# LPC1769.net
KiCad netlist of a schematic drawn in Altium Designer
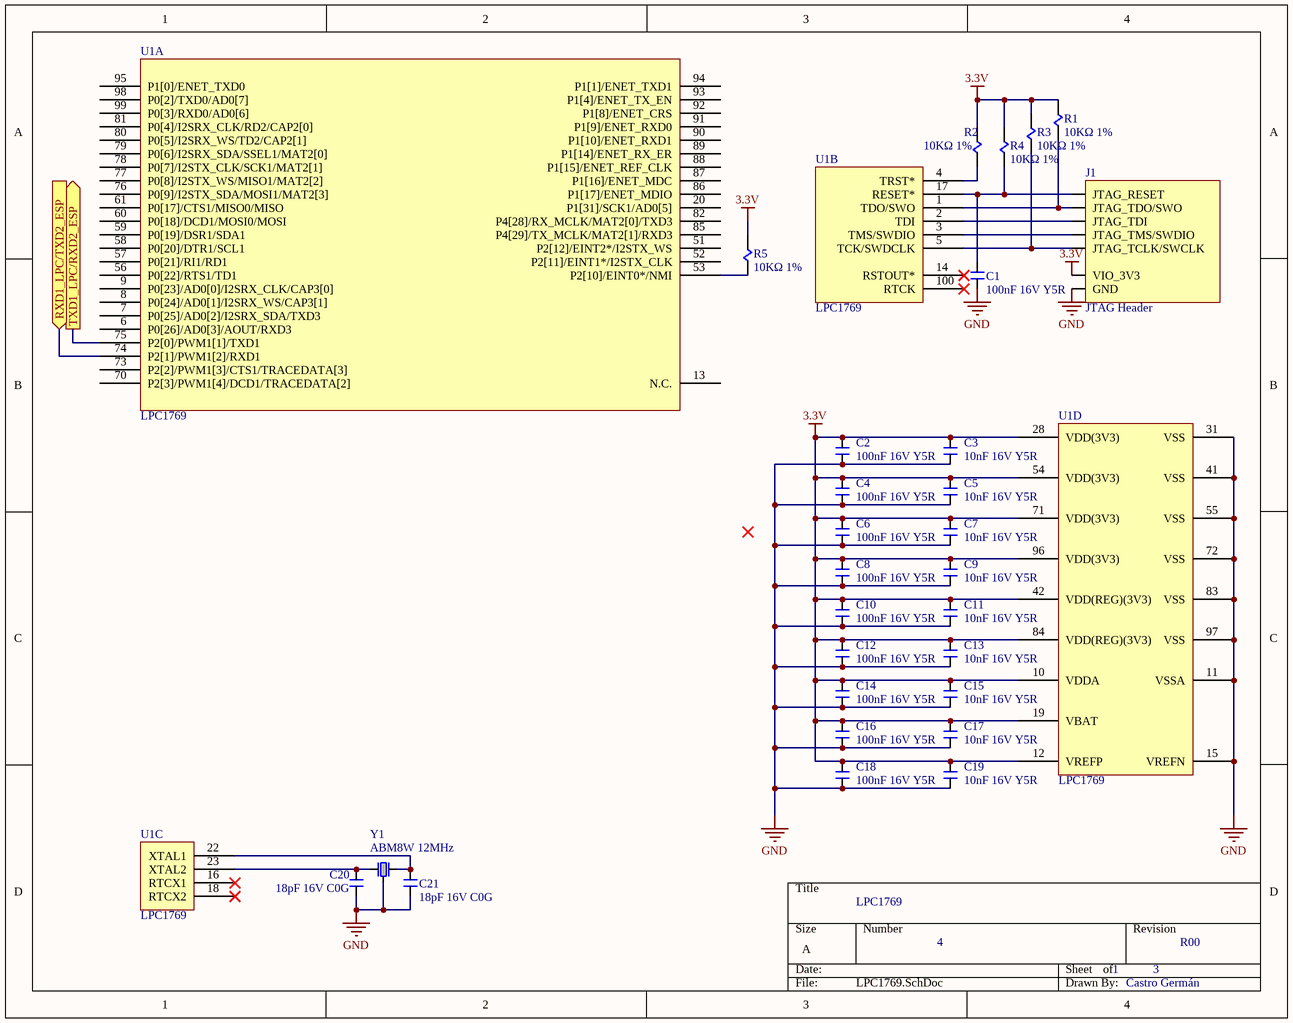
[diagram p0: LPC1769.SchDoc]

(export (version "E")
  (design (tool "Eeschema 10.0.6"))
  (components
    (comp (ref "C1")
      (value "100nF 16V Y5R")
      (footprint "C_0805")
      (description "Capacitor")
      (libsource (lib "MyPro") (part "Capacitor"))
    )
    (comp (ref "C2")
      (value "100nF 16V Y5R")
      (footprint "C_0805")
      (description "Capacitor")
      (libsource (lib "MyPro") (part "Capacitor"))
    )
    (comp (ref "C3")
      (value "10nF 16V Y5R")
      (footprint "C_0805")
      (description "Capacitor")
      (libsource (lib "MyPro") (part "Capacitor"))
    )
    (comp (ref "C4")
      (value "100nF 16V Y5R")
      (footprint "C_0805")
      (description "Capacitor")
      (libsource (lib "MyPro") (part "Capacitor"))
    )
    (comp (ref "C5")
      (value "10nF 16V Y5R")
      (footprint "C_0805")
      (description "Capacitor")
      (libsource (lib "MyPro") (part "Capacitor"))
    )
    (comp (ref "C6")
      (value "100nF 16V Y5R")
      (footprint "C_0805")
      (description "Capacitor")
      (libsource (lib "MyPro") (part "Capacitor"))
    )
    (comp (ref "C7")
      (value "10nF 16V Y5R")
      (footprint "C_0805")
      (description "Capacitor")
      (libsource (lib "MyPro") (part "Capacitor"))
    )
    (comp (ref "C8")
      (value "100nF 16V Y5R")
      (footprint "C_0805")
      (description "Capacitor")
      (libsource (lib "MyPro") (part "Capacitor"))
    )
    (comp (ref "C9")
      (value "10nF 16V Y5R")
      (footprint "C_0805")
      (description "Capacitor")
      (libsource (lib "MyPro") (part "Capacitor"))
    )
    (comp (ref "C10")
      (value "100nF 16V Y5R")
      (footprint "C_0805")
      (description "Capacitor")
      (libsource (lib "MyPro") (part "Capacitor"))
    )
    (comp (ref "C11")
      (value "10nF 16V Y5R")
      (footprint "C_0805")
      (description "Capacitor")
      (libsource (lib "MyPro") (part "Capacitor"))
    )
    (comp (ref "C12")
      (value "100nF 16V Y5R")
      (footprint "C_0805")
      (description "Capacitor")
      (libsource (lib "MyPro") (part "Capacitor"))
    )
    (comp (ref "C13")
      (value "10nF 16V Y5R")
      (footprint "C_0805")
      (description "Capacitor")
      (libsource (lib "MyPro") (part "Capacitor"))
    )
    (comp (ref "C14")
      (value "100nF 16V Y5R")
      (footprint "C_0805")
      (description "Capacitor")
      (libsource (lib "MyPro") (part "Capacitor"))
    )
    (comp (ref "C15")
      (value "10nF 16V Y5R")
      (footprint "C_0805")
      (description "Capacitor")
      (libsource (lib "MyPro") (part "Capacitor"))
    )
    (comp (ref "C16")
      (value "100nF 16V Y5R")
      (footprint "C_0805")
      (description "Capacitor")
      (libsource (lib "MyPro") (part "Capacitor"))
    )
    (comp (ref "C17")
      (value "10nF 16V Y5R")
      (footprint "C_0805")
      (description "Capacitor")
      (libsource (lib "MyPro") (part "Capacitor"))
    )
    (comp (ref "C18")
      (value "100nF 16V Y5R")
      (footprint "C_0805")
      (description "Capacitor")
      (libsource (lib "MyPro") (part "Capacitor"))
    )
    (comp (ref "C19")
      (value "10nF 16V Y5R")
      (footprint "C_0805")
      (description "Capacitor")
      (libsource (lib "MyPro") (part "Capacitor"))
    )
    (comp (ref "C20")
      (value "18pF 16V C0G")
      (footprint "C_0805")
      (description "Capacitor")
      (libsource (lib "MyPro") (part "Capacitor"))
    )
    (comp (ref "C21")
      (value "18pF 16V C0G")
      (footprint "C_0805")
      (description "Capacitor")
      (libsource (lib "MyPro") (part "Capacitor"))
    )
    (comp (ref "J1") (value "JTAG Header") (libsource (lib "MyPro") (part "JTAG Header")))
    (comp (ref "R1")
      (value "10KΩ 1%")
      (footprint "R_0805")
      (description "Resistor")
      (libsource (lib "MyPro") (part "Resistor"))
    )
    (comp (ref "R2")
      (value "10KΩ 1%")
      (footprint "R_0805")
      (description "Resistor")
      (libsource (lib "MyPro") (part "Resistor"))
    )
    (comp (ref "R3")
      (value "10KΩ 1%")
      (footprint "R_0805")
      (description "Resistor")
      (libsource (lib "MyPro") (part "Resistor"))
    )
    (comp (ref "R4")
      (value "10KΩ 1%")
      (footprint "R_0805")
      (description "Resistor")
      (libsource (lib "MyPro") (part "Resistor"))
    )
    (comp (ref "R5")
      (value "10KΩ 1%")
      (footprint "R_0805")
      (description "Resistor")
      (libsource (lib "MyPro") (part "Resistor"))
    )
    (comp (ref "U1")
      (value "LPC1769")
      (footprint "LQFP100")
      (description "32 bit ARM Cortex M3")
      (libsource (lib "MyPro") (part "LPC1769"))
    )
    (comp (ref "Y1")
      (value "ABM8W 12MHz")
      (footprint "ABM8W")
      (description "Crystal")
      (libsource (lib "MyPro") (part "Crystal"))
    )
  )
  (nets
    (net (code "1") (name "/RXD1_LPC{slash}TXD2_ESP") (class "Default")
      (node (ref "U1") (pin "74") (pinfunction "P2[1]/PWM1[2]/RXD1_74") (pintype "passive"))
    )
    (net (code "2") (name "/TXD1_LPC{slash}RXD2_ESP") (class "Default")
      (node (ref "U1") (pin "75") (pinfunction "P2[0]/PWM1[1]/TXD1_75") (pintype "passive"))
    )
    (net (code "3") (name "3.3V") (class "Default")
      (node (ref "C10") (pin "1") (pinfunction "A1_1") (pintype "passive"))
      (node (ref "C11") (pin "1") (pinfunction "A1_1") (pintype "passive"))
      (node (ref "C12") (pin "1") (pinfunction "A1_1") (pintype "passive"))
      (node (ref "C13") (pin "1") (pinfunction "A1_1") (pintype "passive"))
      (node (ref "C14") (pin "1") (pinfunction "A1_1") (pintype "passive"))
      (node (ref "C15") (pin "1") (pinfunction "A1_1") (pintype "passive"))
      (node (ref "C16") (pin "1") (pinfunction "A1_1") (pintype "passive"))
      (node (ref "C17") (pin "1") (pinfunction "A1_1") (pintype "passive"))
      (node (ref "C18") (pin "1") (pinfunction "A1_1") (pintype "passive"))
      (node (ref "C19") (pin "1") (pinfunction "A1_1") (pintype "passive"))
      (node (ref "C2") (pin "1") (pinfunction "A1_1") (pintype "passive"))
      (node (ref "C3") (pin "1") (pinfunction "A1_1") (pintype "passive"))
      (node (ref "C4") (pin "1") (pinfunction "A1_1") (pintype "passive"))
      (node (ref "C5") (pin "1") (pinfunction "A1_1") (pintype "passive"))
      (node (ref "C6") (pin "1") (pinfunction "A1_1") (pintype "passive"))
      (node (ref "C7") (pin "1") (pinfunction "A1_1") (pintype "passive"))
      (node (ref "C8") (pin "1") (pinfunction "A1_1") (pintype "passive"))
      (node (ref "C9") (pin "1") (pinfunction "A1_1") (pintype "passive"))
      (node (ref "J1") (pin "1") (pinfunction "VIO_3V3_1") (pintype "passive"))
      (node (ref "R1") (pin "2") (pinfunction "P2_2") (pintype "passive"))
      (node (ref "R2") (pin "2") (pinfunction "P2_2") (pintype "passive"))
      (node (ref "R3") (pin "2") (pinfunction "P2_2") (pintype "passive"))
      (node (ref "R4") (pin "2") (pinfunction "P2_2") (pintype "passive"))
      (node (ref "R5") (pin "1") (pinfunction "P1_1") (pintype "passive"))
      (node (ref "U1") (pin "10") (pinfunction "VDDA_10") (pintype "passive"))
      (node (ref "U1") (pin "12") (pinfunction "VREFP_12") (pintype "passive"))
      (node (ref "U1") (pin "19") (pinfunction "VBAT_19") (pintype "passive"))
      (node (ref "U1") (pin "28") (pinfunction "VDD(3V3)_28") (pintype "passive"))
      (node (ref "U1") (pin "42") (pinfunction "VDD(REG)(3V3)_42") (pintype "passive"))
      (node (ref "U1") (pin "54") (pinfunction "VDD(3V3)_54") (pintype "passive"))
      (node (ref "U1") (pin "71") (pinfunction "VDD(3V3)_71") (pintype "passive"))
      (node (ref "U1") (pin "84") (pinfunction "VDD(REG)(3V3)_84") (pintype "passive"))
      (node (ref "U1") (pin "96") (pinfunction "VDD(3V3)_96") (pintype "passive"))
    )
    (net (code "4") (name "GND") (class "Default")
      (node (ref "C1") (pin "2") (pinfunction "A2_2") (pintype "passive"))
      (node (ref "C10") (pin "2") (pinfunction "A2_2") (pintype "passive"))
      (node (ref "C11") (pin "2") (pinfunction "A2_2") (pintype "passive"))
      (node (ref "C12") (pin "2") (pinfunction "A2_2") (pintype "passive"))
      (node (ref "C13") (pin "2") (pinfunction "A2_2") (pintype "passive"))
      (node (ref "C14") (pin "2") (pinfunction "A2_2") (pintype "passive"))
      (node (ref "C15") (pin "2") (pinfunction "A2_2") (pintype "passive"))
      (node (ref "C16") (pin "2") (pinfunction "A2_2") (pintype "passive"))
      (node (ref "C17") (pin "2") (pinfunction "A2_2") (pintype "passive"))
      (node (ref "C18") (pin "2") (pinfunction "A2_2") (pintype "passive"))
      (node (ref "C19") (pin "2") (pinfunction "A2_2") (pintype "passive"))
      (node (ref "C2") (pin "2") (pinfunction "A2_2") (pintype "passive"))
      (node (ref "C20") (pin "2") (pinfunction "A2_2") (pintype "passive"))
      (node (ref "C21") (pin "2") (pinfunction "A2_2") (pintype "passive"))
      (node (ref "C3") (pin "2") (pinfunction "A2_2") (pintype "passive"))
      (node (ref "C4") (pin "2") (pinfunction "A2_2") (pintype "passive"))
      (node (ref "C5") (pin "2") (pinfunction "A2_2") (pintype "passive"))
      (node (ref "C6") (pin "2") (pinfunction "A2_2") (pintype "passive"))
      (node (ref "C7") (pin "2") (pinfunction "A2_2") (pintype "passive"))
      (node (ref "C8") (pin "2") (pinfunction "A2_2") (pintype "passive"))
      (node (ref "C9") (pin "2") (pinfunction "A2_2") (pintype "passive"))
      (node (ref "J1") (pin "8") (pinfunction "GND_8") (pintype "passive"))
      (node (ref "U1") (pin "11") (pinfunction "VSSA_11") (pintype "passive"))
      (node (ref "U1") (pin "15") (pinfunction "VREFN_15") (pintype "passive"))
      (node (ref "U1") (pin "31") (pinfunction "VSS_31") (pintype "passive"))
      (node (ref "U1") (pin "41") (pinfunction "VSS_41") (pintype "passive"))
      (node (ref "U1") (pin "55") (pinfunction "VSS_55") (pintype "passive"))
      (node (ref "U1") (pin "72") (pinfunction "VSS_72") (pintype "passive"))
      (node (ref "U1") (pin "83") (pinfunction "VSS_83") (pintype "passive"))
      (node (ref "U1") (pin "97") (pinfunction "VSS_97") (pintype "passive"))
      (node (ref "Y1") (pin "3") (pinfunction "P3_3") (pintype "passive"))
    )
    (net (code "5") (name "Net-(C1-A1)") (class "Default")
      (node (ref "C1") (pin "1") (pinfunction "A1_1") (pintype "passive"))
      (node (ref "J1") (pin "6") (pinfunction "JTAG_RESET_6") (pintype "passive"))
      (node (ref "R4") (pin "1") (pinfunction "P1_1") (pintype "passive"))
      (node (ref "U1") (pin "17") (pinfunction "RESET*_17") (pintype "passive"))
    )
    (net (code "6") (name "Net-(C20-A1)") (class "Default")
      (node (ref "C20") (pin "1") (pinfunction "A1_1") (pintype "passive"))
      (node (ref "U1") (pin "23") (pinfunction "XTAL2_23") (pintype "passive"))
      (node (ref "Y1") (pin "1") (pinfunction "P1_1") (pintype "passive"))
    )
    (net (code "7") (name "Net-(C21-A1)") (class "Default")
      (node (ref "C21") (pin "1") (pinfunction "A1_1") (pintype "passive"))
      (node (ref "U1") (pin "22") (pinfunction "XTAL1_22") (pintype "passive"))
      (node (ref "Y1") (pin "2") (pinfunction "P2_2") (pintype "passive"))
    )
    (net (code "8") (name "Net-(J1-JTAG_TCLK{slash}SWCLK)") (class "Default")
      (node (ref "J1") (pin "3") (pinfunction "JTAG_TCLK/SWCLK_3") (pintype "passive"))
      (node (ref "R3") (pin "1") (pinfunction "P1_1") (pintype "passive"))
      (node (ref "U1") (pin "5") (pinfunction "TCK/SWDCLK_5") (pintype "passive"))
    )
    (net (code "9") (name "Net-(J1-JTAG_TDI)") (class "Default")
      (node (ref "J1") (pin "5") (pinfunction "JTAG_TDI_5") (pintype "passive"))
      (node (ref "U1") (pin "2") (pinfunction "TDI_2") (pintype "passive"))
    )
    (net (code "10") (name "Net-(J1-JTAG_TDO{slash}SWO)") (class "Default")
      (node (ref "J1") (pin "4") (pinfunction "JTAG_TDO/SWO_4") (pintype "passive"))
      (node (ref "R1") (pin "1") (pinfunction "P1_1") (pintype "passive"))
      (node (ref "U1") (pin "1") (pinfunction "TDO/SWO_1") (pintype "passive"))
    )
    (net (code "11") (name "Net-(J1-JTAG_TMS{slash}SWDIO)") (class "Default")
      (node (ref "J1") (pin "2") (pinfunction "JTAG_TMS/SWDIO_2") (pintype "passive"))
      (node (ref "U1") (pin "3") (pinfunction "TMS/SWDIO_3") (pintype "passive"))
    )
    (net (code "12") (name "Net-(R2-P1)") (class "Default")
      (node (ref "R2") (pin "1") (pinfunction "P1_1") (pintype "passive"))
      (node (ref "U1") (pin "4") (pinfunction "TRST*_4") (pintype "passive"))
    )
    (net (code "13") (name "Net-(R5-P2)") (class "Default")
      (node (ref "R5") (pin "2") (pinfunction "P2_2") (pintype "passive"))
      (node (ref "U1") (pin "53") (pinfunction "P2[10]/EINT0*/NMI_53") (pintype "passive"))
    )
    (net (code "14") (name "unconnected-(U1A-N.C.-Pad13)") (class "Default")
      (node (ref "U1") (pin "13") (pinfunction "N.C._13") (pintype "passive"))
    )
    (net (code "15") (name "unconnected-(U1A-P0[2]{slash}TXD0{slash}AD0[7]-Pad98)") (class "Default")
      (node (ref "U1") (pin "98") (pinfunction "P0[2]/TXD0/AD0[7]_98") (pintype "passive"))
    )
    (net (code "16") (name "unconnected-(U1A-P0[3]{slash}RXD0{slash}AD0[6]-Pad99)") (class "Default")
      (node (ref "U1") (pin "99") (pinfunction "P0[3]/RXD0/AD0[6]_99") (pintype "passive"))
    )
    (net (code "17") (name "unconnected-(U1A-P0[4]{slash}I2SRX_CLK{slash}RD2{slash}CAP2[0]-Pad81)") (class "Default")
      (node (ref "U1") (pin "81") (pinfunction "P0[4]/I2SRX_CLK/RD2/CAP2[0]_81") (pintype "passive"))
    )
    (net (code "18") (name "unconnected-(U1A-P0[5]{slash}I2SRX_WS{slash}TD2{slash}CAP2[1]-Pad80)") (class "Default")
      (node (ref "U1") (pin "80") (pinfunction "P0[5]/I2SRX_WS/TD2/CAP2[1]_80") (pintype "passive"))
    )
    (net (code "19") (name "unconnected-(U1A-P0[6]{slash}I2SRX_SDA{slash}SSEL1{slash}MAT2[0]-Pad79)") (class "Default")
      (node (ref "U1") (pin "79") (pinfunction "P0[6]/I2SRX_SDA/SSEL1/MAT2[0]_79") (pintype "passive"))
    )
    (net (code "20") (name "unconnected-(U1A-P0[7]{slash}I2STX_CLK{slash}SCK1{slash}MAT2[1]-Pad78)") (class "Default")
      (node (ref "U1") (pin "78") (pinfunction "P0[7]/I2STX_CLK/SCK1/MAT2[1]_78") (pintype "passive"))
    )
    (net (code "21") (name "unconnected-(U1A-P0[8]{slash}I2STX_WS{slash}MISO1{slash}MAT2[2]-Pad77)") (class "Default")
      (node (ref "U1") (pin "77") (pinfunction "P0[8]/I2STX_WS/MISO1/MAT2[2]_77") (pintype "passive"))
    )
    (net (code "22") (name "unconnected-(U1A-P0[9]{slash}I2STX_SDA{slash}MOSI1{slash}MAT2[3]-Pad76)") (class "Default")
      (node (ref "U1") (pin "76") (pinfunction "P0[9]/I2STX_SDA/MOSI1/MAT2[3]_76") (pintype "passive"))
    )
    (net (code "23") (name "unconnected-(U1A-P0[17]{slash}CTS1{slash}MISO0{slash}MISO-Pad61)") (class "Default")
      (node (ref "U1") (pin "61") (pinfunction "P0[17]/CTS1/MISO0/MISO_61") (pintype "passive"))
    )
    (net (code "24") (name "unconnected-(U1A-P0[18]{slash}DCD1{slash}MOSI0{slash}MOSI-Pad60)") (class "Default")
      (node (ref "U1") (pin "60") (pinfunction "P0[18]/DCD1/MOSI0/MOSI_60") (pintype "passive"))
    )
    (net (code "25") (name "unconnected-(U1A-P0[19]{slash}DSR1{slash}SDA1-Pad59)") (class "Default")
      (node (ref "U1") (pin "59") (pinfunction "P0[19]/DSR1/SDA1_59") (pintype "passive"))
    )
    (net (code "26") (name "unconnected-(U1A-P0[20]{slash}DTR1{slash}SCL1-Pad58)") (class "Default")
      (node (ref "U1") (pin "58") (pinfunction "P0[20]/DTR1/SCL1_58") (pintype "passive"))
    )
    (net (code "27") (name "unconnected-(U1A-P0[21]{slash}RI1{slash}RD1-Pad57)") (class "Default")
      (node (ref "U1") (pin "57") (pinfunction "P0[21]/RI1/RD1_57") (pintype "passive"))
    )
    (net (code "28") (name "unconnected-(U1A-P0[22]{slash}RTS1{slash}TD1-Pad56)") (class "Default")
      (node (ref "U1") (pin "56") (pinfunction "P0[22]/RTS1/TD1_56") (pintype "passive"))
    )
    (net (code "29") (name "unconnected-(U1A-P0[23]{slash}AD0[0]{slash}I2SRX_CLK{slash}CAP3[0]-Pad9)") (class "Default")
      (node (ref "U1") (pin "9") (pinfunction "P0[23]/AD0[0]/I2SRX_CLK/CAP3[0]_9") (pintype "passive"))
    )
    (net (code "30") (name "unconnected-(U1A-P0[24]{slash}AD0[1]{slash}I2SRX_WS{slash}CAP3[1]-Pad8)") (class "Default")
      (node (ref "U1") (pin "8") (pinfunction "P0[24]/AD0[1]/I2SRX_WS/CAP3[1]_8") (pintype "passive"))
    )
    (net (code "31") (name "unconnected-(U1A-P0[25]{slash}AD0[2]{slash}I2SRX_SDA{slash}TXD3-Pad7)") (class "Default")
      (node (ref "U1") (pin "7") (pinfunction "P0[25]/AD0[2]/I2SRX_SDA/TXD3_7") (pintype "passive"))
    )
    (net (code "32") (name "unconnected-(U1A-P0[26]{slash}AD0[3]{slash}AOUT{slash}RXD3-Pad6)") (class "Default")
      (node (ref "U1") (pin "6") (pinfunction "P0[26]/AD0[3]/AOUT/RXD3_6") (pintype "passive"))
    )
    (net (code "33") (name "unconnected-(U1A-P1[0]{slash}ENET_TXD0-Pad95)") (class "Default")
      (node (ref "U1") (pin "95") (pinfunction "P1[0]/ENET_TXD0_95") (pintype "passive"))
    )
    (net (code "34") (name "unconnected-(U1A-P1[1]{slash}ENET_TXD1-Pad94)") (class "Default")
      (node (ref "U1") (pin "94") (pinfunction "P1[1]/ENET_TXD1_94") (pintype "passive"))
    )
    (net (code "35") (name "unconnected-(U1A-P1[4]{slash}ENET_TX_EN-Pad93)") (class "Default")
      (node (ref "U1") (pin "93") (pinfunction "P1[4]/ENET_TX_EN_93") (pintype "passive"))
    )
    (net (code "36") (name "unconnected-(U1A-P1[8]{slash}ENET_CRS-Pad92)") (class "Default")
      (node (ref "U1") (pin "92") (pinfunction "P1[8]/ENET_CRS_92") (pintype "passive"))
    )
    (net (code "37") (name "unconnected-(U1A-P1[9]{slash}ENET_RXD0-Pad91)") (class "Default")
      (node (ref "U1") (pin "91") (pinfunction "P1[9]/ENET_RXD0_91") (pintype "passive"))
    )
    (net (code "38") (name "unconnected-(U1A-P1[10]{slash}ENET_RXD1-Pad90)") (class "Default")
      (node (ref "U1") (pin "90") (pinfunction "P1[10]/ENET_RXD1_90") (pintype "passive"))
    )
    (net (code "39") (name "unconnected-(U1A-P1[14]{slash}ENET_RX_ER-Pad89)") (class "Default")
      (node (ref "U1") (pin "89") (pinfunction "P1[14]/ENET_RX_ER_89") (pintype "passive"))
    )
    (net (code "40") (name "unconnected-(U1A-P1[15]{slash}ENET_REF_CLK-Pad88)") (class "Default")
      (node (ref "U1") (pin "88") (pinfunction "P1[15]/ENET_REF_CLK_88") (pintype "passive"))
    )
    (net (code "41") (name "unconnected-(U1A-P1[16]{slash}ENET_MDC-Pad87)") (class "Default")
      (node (ref "U1") (pin "87") (pinfunction "P1[16]/ENET_MDC_87") (pintype "passive"))
    )
    (net (code "42") (name "unconnected-(U1A-P1[17]{slash}ENET_MDIO-Pad86)") (class "Default")
      (node (ref "U1") (pin "86") (pinfunction "P1[17]/ENET_MDIO_86") (pintype "passive"))
    )
    (net (code "43") (name "unconnected-(U1A-P1[31]{slash}SCK1{slash}AD0[5]-Pad20)") (class "Default")
      (node (ref "U1") (pin "20") (pinfunction "P1[31]/SCK1/AD0[5]_20") (pintype "passive"))
    )
    (net (code "44") (name "unconnected-(U1A-P2[2]{slash}PWM1[3]{slash}CTS1{slash}TRACEDATA[3]-Pad73)") (class "Default")
      (node (ref "U1") (pin "73") (pinfunction "P2[2]/PWM1[3]/CTS1/TRACEDATA[3]_73") (pintype "passive"))
    )
    (net (code "45") (name "unconnected-(U1A-P2[3]{slash}PWM1[4]{slash}DCD1{slash}TRACEDATA[2]-Pad70)") (class "Default")
      (node (ref "U1") (pin "70") (pinfunction "P2[3]/PWM1[4]/DCD1/TRACEDATA[2]_70") (pintype "passive"))
    )
    (net (code "46") (name "unconnected-(U1A-P2[11]{slash}EINT1*{slash}I2STX_CLK-Pad52)") (class "Default")
      (node (ref "U1") (pin "52") (pinfunction "P2[11]/EINT1*/I2STX_CLK_52") (pintype "passive"))
    )
    (net (code "47") (name "unconnected-(U1A-P2[12]{slash}EINT2*{slash}I2STX_WS-Pad51)") (class "Default")
      (node (ref "U1") (pin "51") (pinfunction "P2[12]/EINT2*/I2STX_WS_51") (pintype "passive"))
    )
    (net (code "48") (name "unconnected-(U1A-P4[28]{slash}RX_MCLK{slash}MAT2[0]{slash}TXD3-Pad82)") (class "Default")
      (node (ref "U1") (pin "82") (pinfunction "P4[28]/RX_MCLK/MAT2[0]/TXD3_82") (pintype "passive"))
    )
    (net (code "49") (name "unconnected-(U1A-P4[29]{slash}TX_MCLK{slash}MAT2[1]{slash}RXD3-Pad85)") (class "Default")
      (node (ref "U1") (pin "85") (pinfunction "P4[29]/TX_MCLK/MAT2[1]/RXD3_85") (pintype "passive"))
    )
    (net (code "50") (name "unconnected-(U1B-RSTOUT*-Pad14)") (class "Default")
      (node (ref "U1") (pin "14") (pinfunction "RSTOUT*_14") (pintype "passive+no_connect"))
    )
    (net (code "51") (name "unconnected-(U1B-RTCK-Pad100)") (class "Default")
      (node (ref "U1") (pin "100") (pinfunction "RTCK_100") (pintype "passive+no_connect"))
    )
    (net (code "52") (name "unconnected-(U1C-RTCX1-Pad16)") (class "Default")
      (node (ref "U1") (pin "16") (pinfunction "RTCX1_16") (pintype "passive+no_connect"))
    )
    (net (code "53") (name "unconnected-(U1C-RTCX2-Pad18)") (class "Default")
      (node (ref "U1") (pin "18") (pinfunction "RTCX2_18") (pintype "passive+no_connect"))
    )
  )
)
